# Power_Switching_Circuit_rev4.net
KiCad netlist of a schematic drawn in EAGLE
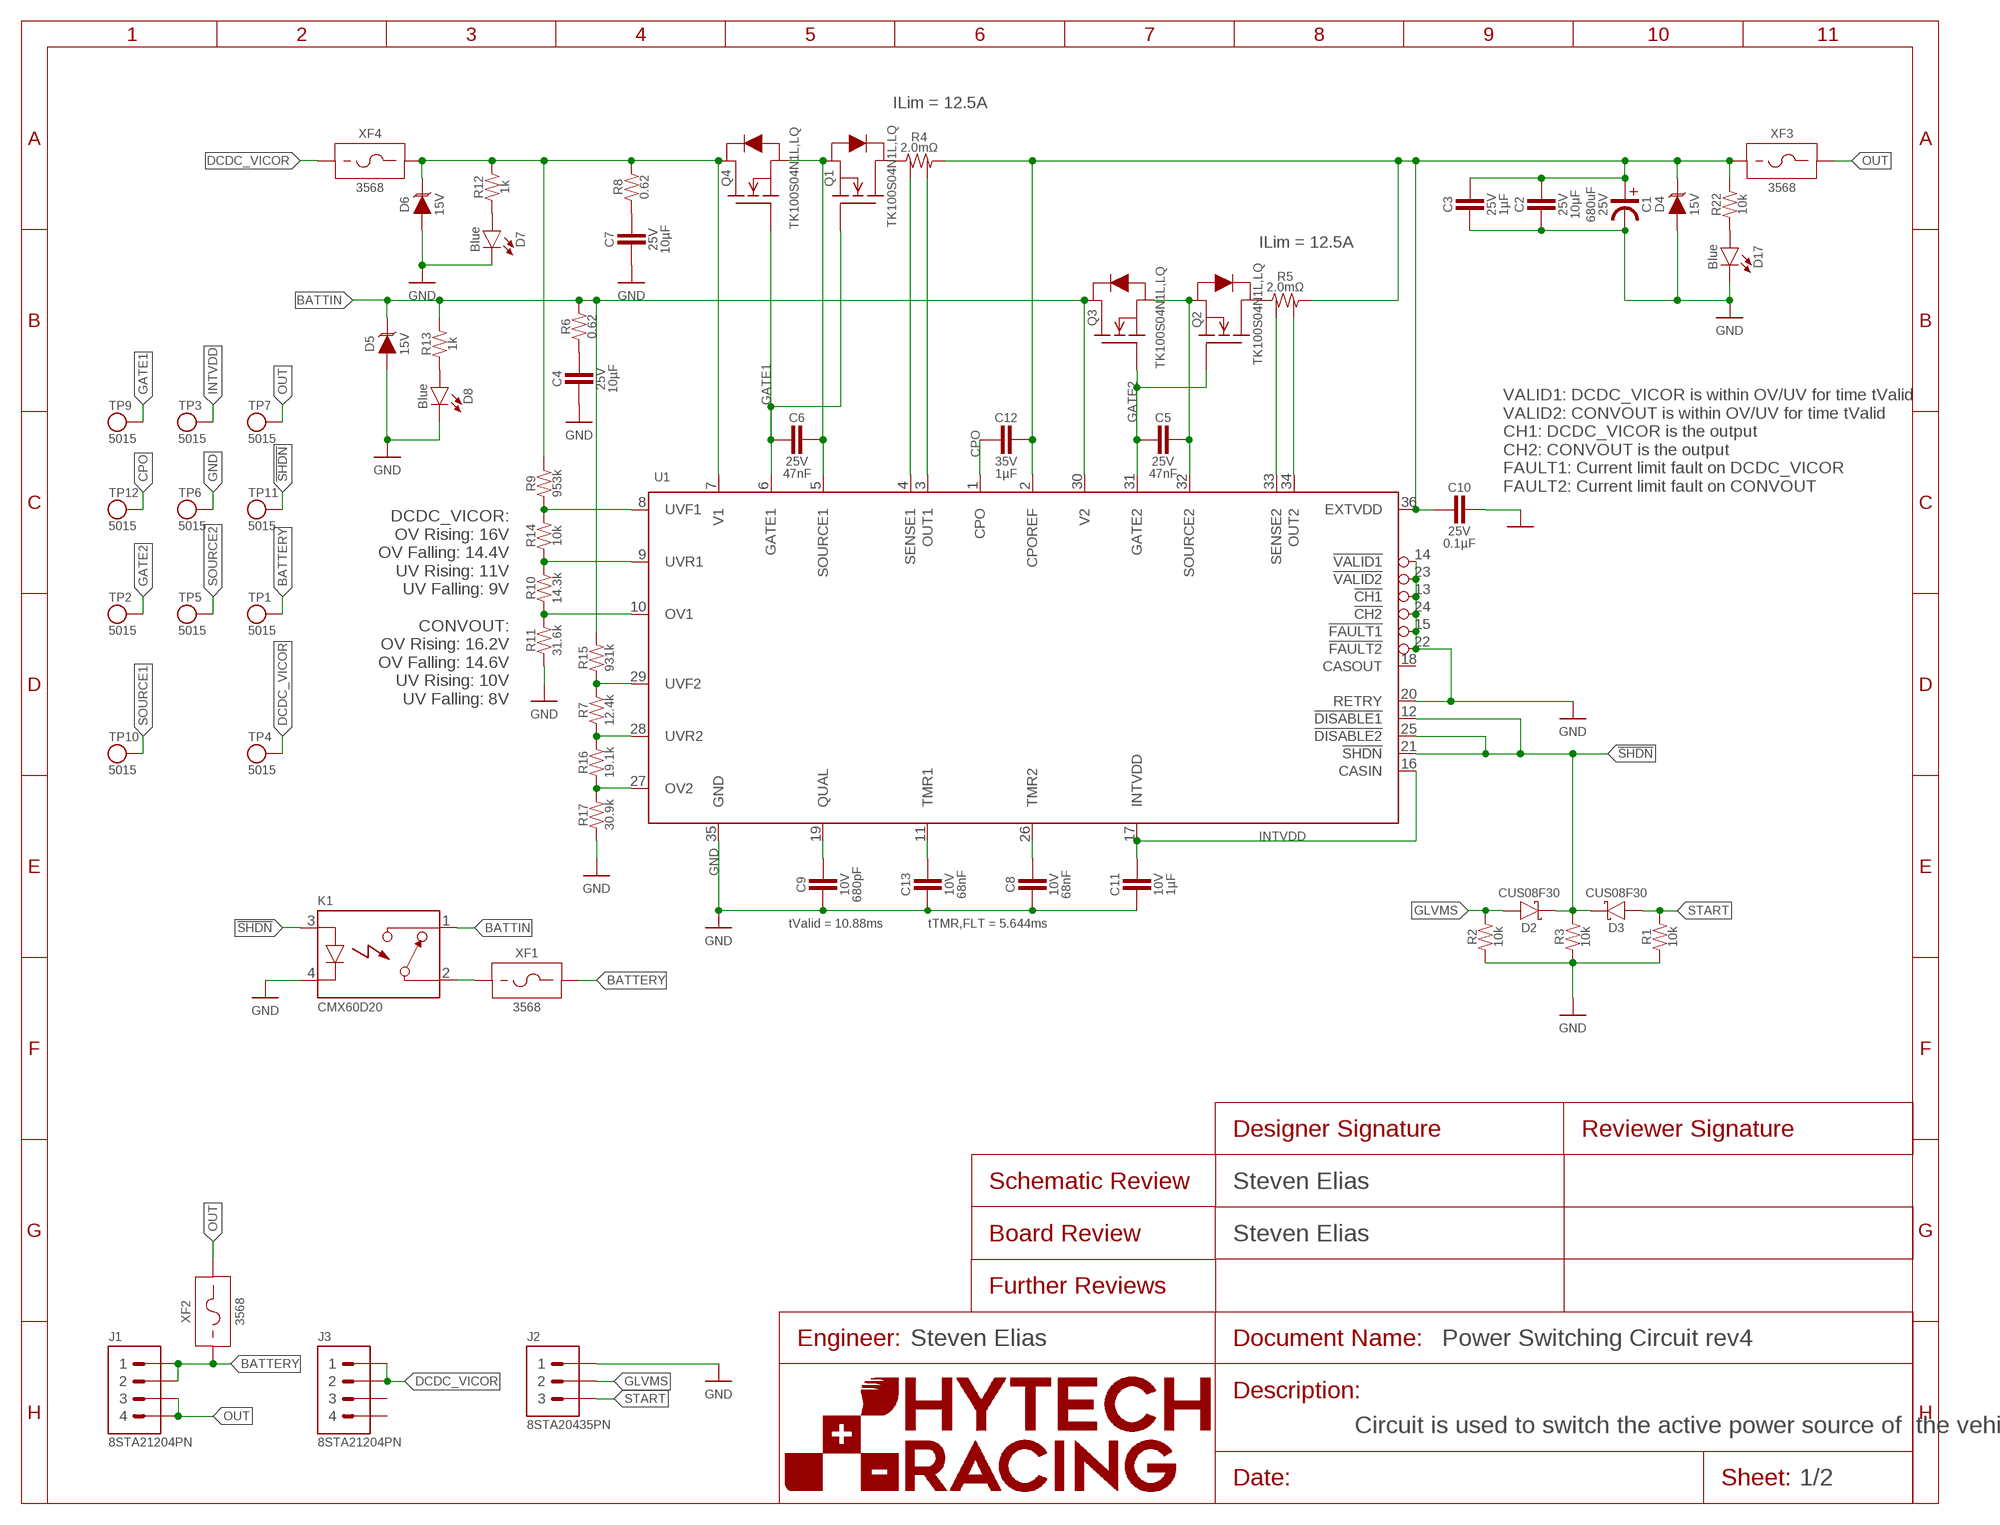
[diagram p0: schematic, sheet 1]
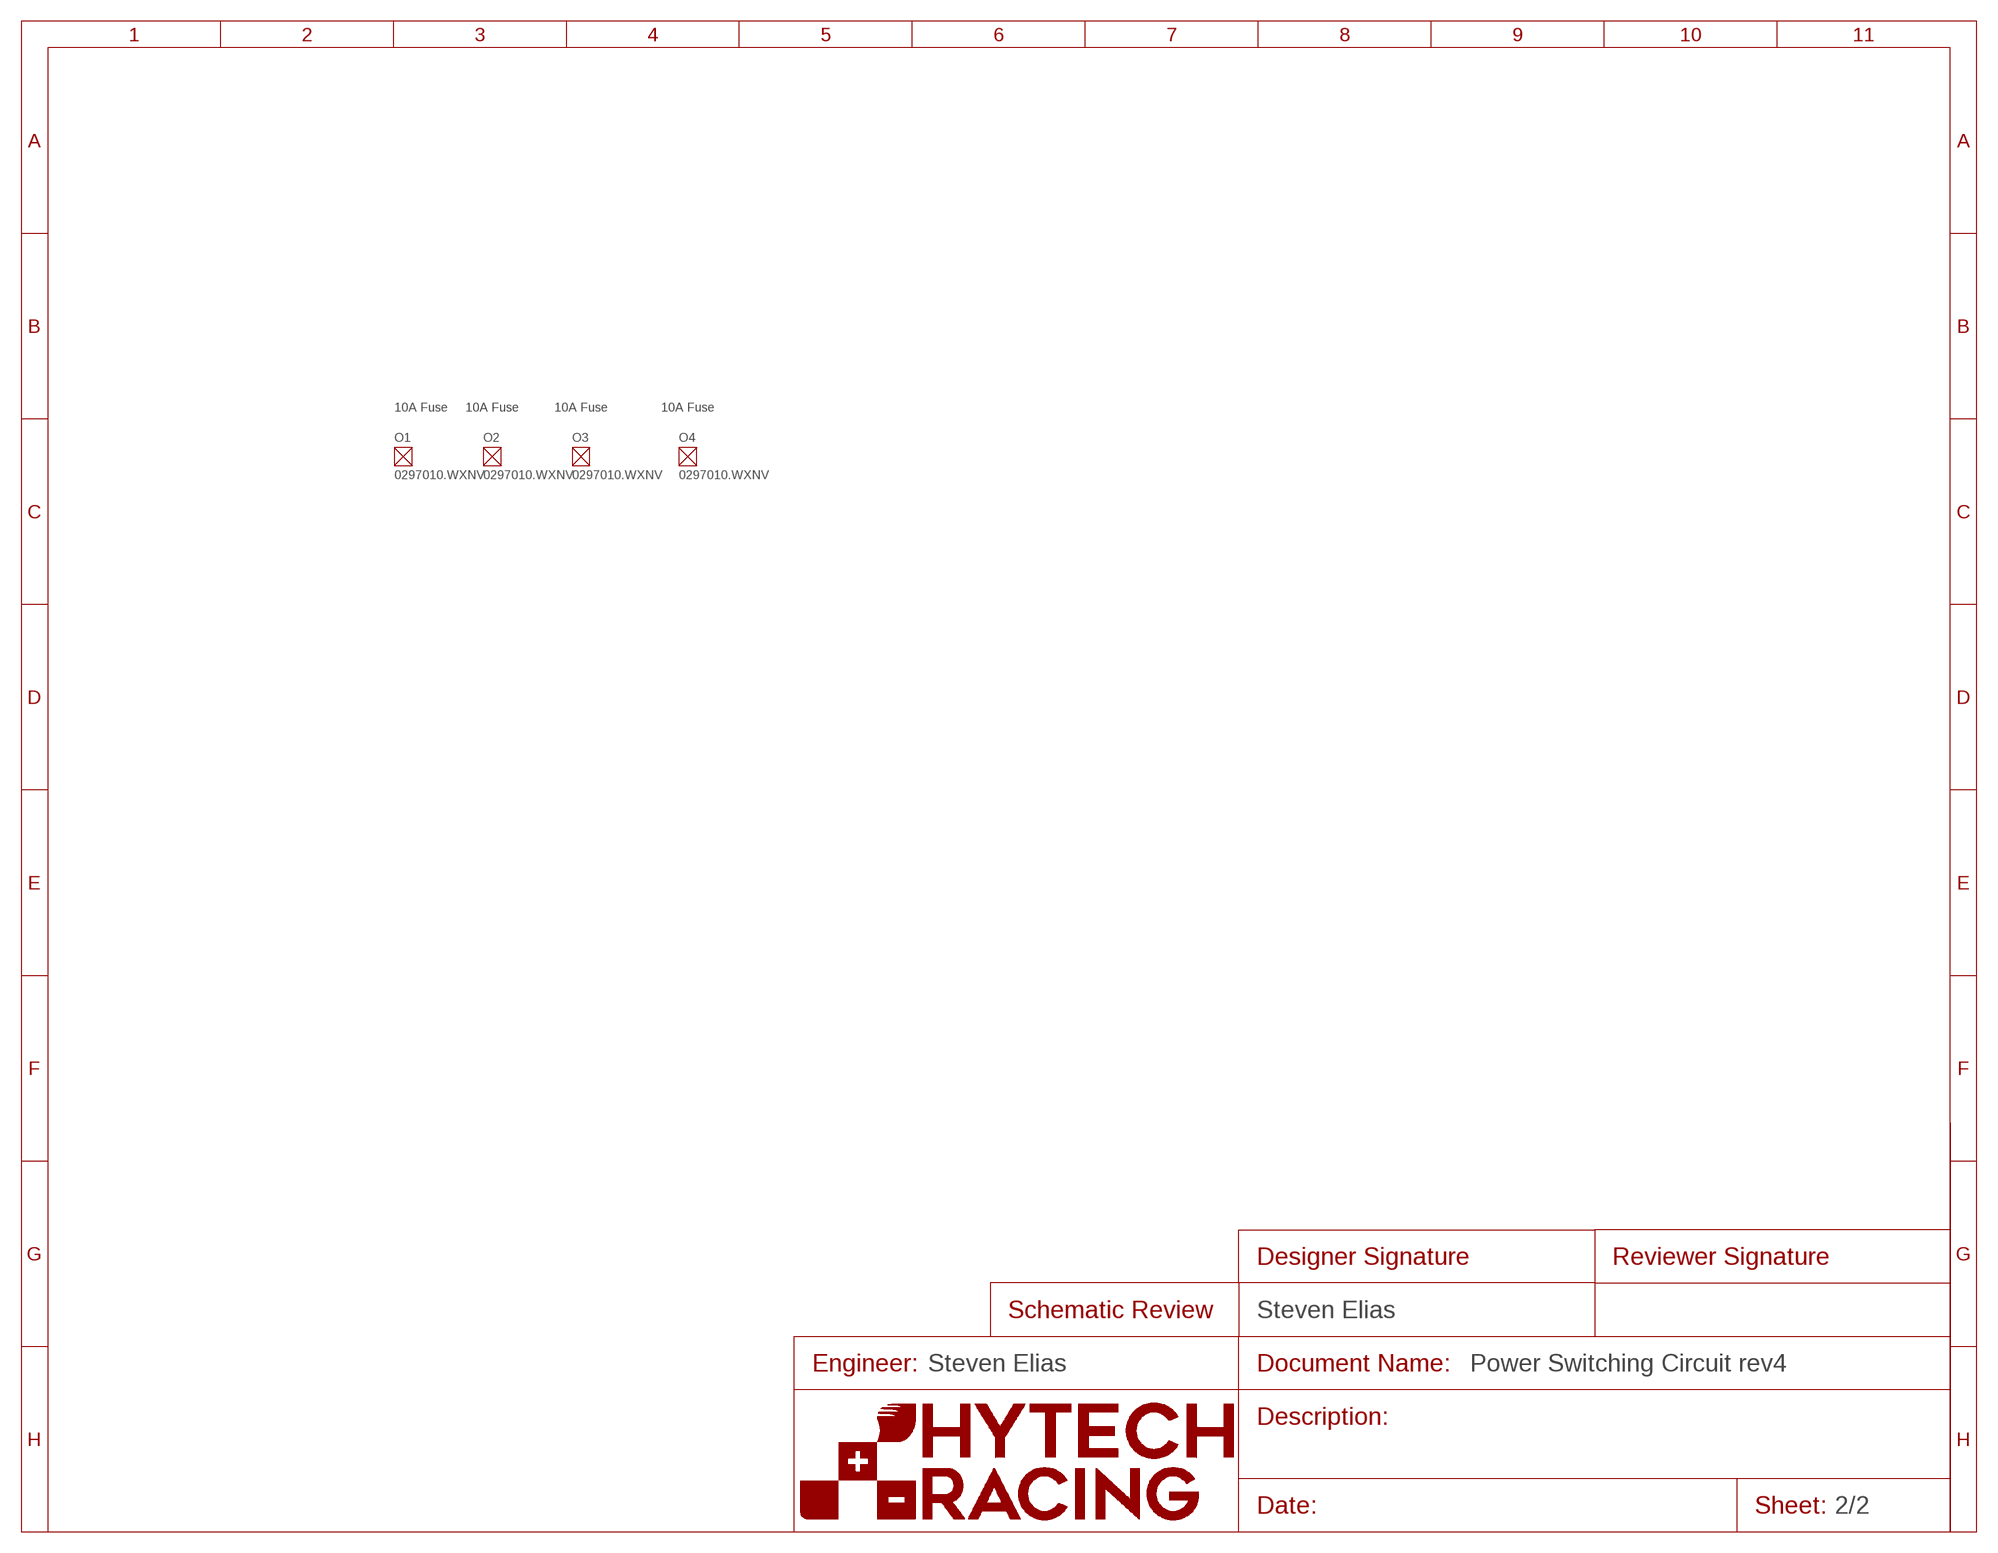
[diagram p1: schematic, sheet 2]

(export (version "E")
  (design (tool "Eeschema 10.0.6"))
  (components
    (comp (ref "C1")
      (value "EEUFP1E681")
      (footprint "eagle-import:EEUFP1E_")
      (fields
        (field (name "CAPACITANCE") "680uF")
        (field (name "MANUFACTURER") "Panasonic Electronic Components")
        (field (name "MPN") "EEU-FP1E681")
        (field (name "TOLERANCE") "20%")
        (field (name "VOLTAGE") "25V")
      )
      (libsource (lib "eagle-import") (part "EEUFP1E681"))
    )
    (comp (ref "C2")
      (value "CAPACITOR_0603_25V_10UF")
      (footprint "eagle-import:0603-CAP")
      (fields
        (field (name "CAPACITANCE") "10µF")
        (field (name "MANUFACTURER") "Murata Electronics")
        (field (name "MPN") "GRM188R61E106MA73D")
        (field (name "TOLERANCE") "20%")
        (field (name "VOLTAGE") "25V")
      )
      (libsource (lib "eagle-import") (part "CAPACITOR_?_060325V_10UF"))
    )
    (comp (ref "C3")
      (value "CAPACITOR_0603_25V_1UF")
      (footprint "eagle-import:0603-CAP")
      (fields
        (field (name "CAPACITANCE") "1µF")
        (field (name "MANUFACTURER") "Samsung Electro-Mechanics")
        (field (name "MPN") "CL10B105KA8NNNC")
        (field (name "TOLERANCE") "10%")
        (field (name "VOLTAGE") "25V")
      )
      (libsource (lib "eagle-import") (part "CAPACITOR_?_060325V_1UF"))
    )
    (comp (ref "C4")
      (value "CAPACITOR_0603_25V_10UF")
      (footprint "eagle-import:0603-CAP")
      (fields
        (field (name "CAPACITANCE") "10µF")
        (field (name "MANUFACTURER") "Murata Electronics")
        (field (name "MPN") "GRM188R61E106MA73D")
        (field (name "TOLERANCE") "20%")
        (field (name "VOLTAGE") "25V")
      )
      (libsource (lib "eagle-import") (part "CAPACITOR_?_060325V_10UF"))
    )
    (comp (ref "C5")
      (value "CAPACITOR_0603_25V_47NF")
      (footprint "eagle-import:0603-CAP")
      (fields
        (field (name "CAPACITANCE") "47nF")
        (field (name "MANUFACTURER") "Kyocera AVX")
        (field (name "MPN") "06033C473K4Z2A")
        (field (name "TOLERANCE") "10%")
        (field (name "VOLTAGE") "25V")
      )
      (libsource (lib "eagle-import") (part "CAPACITOR_?_060325V_47NF"))
    )
    (comp (ref "C6")
      (value "CAPACITOR_0603_25V_47NF")
      (footprint "eagle-import:0603-CAP")
      (fields
        (field (name "CAPACITANCE") "47nF")
        (field (name "MANUFACTURER") "Kyocera AVX")
        (field (name "MPN") "06033C473K4Z2A")
        (field (name "TOLERANCE") "10%")
        (field (name "VOLTAGE") "25V")
      )
      (libsource (lib "eagle-import") (part "CAPACITOR_?_060325V_47NF"))
    )
    (comp (ref "C7")
      (value "CAPACITOR_0603_25V_10UF")
      (footprint "eagle-import:0603-CAP")
      (fields
        (field (name "CAPACITANCE") "10µF")
        (field (name "MANUFACTURER") "Murata Electronics")
        (field (name "MPN") "GRM188R61E106MA73D")
        (field (name "TOLERANCE") "20%")
        (field (name "VOLTAGE") "25V")
      )
      (libsource (lib "eagle-import") (part "CAPACITOR_?_060325V_10UF"))
    )
    (comp (ref "C8")
      (value "CAPACITOR_0603_10V_68NF")
      (footprint "eagle-import:0603-CAP")
      (fields
        (field (name "CAPACITANCE") "68nF")
        (field (name "MANUFACTURER") "KEMET")
        (field (name "MPN") "C0603C683K8RACTU")
        (field (name "TOLERANCE") "10%")
        (field (name "VOLTAGE") "10V")
      )
      (libsource (lib "eagle-import") (part "CAPACITOR_?_060310V_68NF"))
    )
    (comp (ref "C9")
      (value "CAPACITOR_0603_10V_680PF")
      (footprint "eagle-import:0603-CAP")
      (fields
        (field (name "CAPACITANCE") "680pF")
        (field (name "MANUFACTURER") "Würth Elektronik")
        (field (name "MPN") "885012006013")
        (field (name "TOLERANCE") "5%")
        (field (name "VOLTAGE") "10V")
      )
      (libsource (lib "eagle-import") (part "CAPACITOR_?_060310V_680PF"))
    )
    (comp (ref "C10")
      (value "CAPACITOR_0603_25V_0.1UF")
      (footprint "eagle-import:0603-CAP")
      (fields
        (field (name "CAPACITANCE") "0.1µF")
        (field (name "MANUFACTURER") "Samsung Electro-Mechanics")
        (field (name "MPN") "CL10B104KA8NNNC")
        (field (name "TOLERANCE") "10%")
        (field (name "VOLTAGE") "25V")
      )
      (libsource (lib "eagle-import") (part "CAPACITOR_?_060325V_0.1UF"))
    )
    (comp (ref "C11")
      (value "CAPACITOR_0603_10V_1UF")
      (footprint "eagle-import:0603-CAP")
      (fields
        (field (name "CAPACITANCE") "1µF")
        (field (name "MANUFACTURER") "Yageo")
        (field (name "MPN") "CC0603KRX7R6BB105")
        (field (name "TOLERANCE") "10%")
        (field (name "VOLTAGE") "10V")
      )
      (libsource (lib "eagle-import") (part "CAPACITOR_?_060310V_1UF"))
    )
    (comp (ref "C12")
      (value "CAPACITOR_0603_35V_1UF")
      (footprint "eagle-import:0603-CAP")
      (fields
        (field (name "CAPACITANCE") "1µF")
        (field (name "MANUFACTURER") "TDK Corporation")
        (field (name "MPN") "C1608X7R1V105K080AE")
        (field (name "TOLERANCE") "10%")
        (field (name "VOLTAGE") "35V")
      )
      (libsource (lib "eagle-import") (part "CAPACITOR_?_060335V_1UF"))
    )
    (comp (ref "C13")
      (value "CAPACITOR_0603_10V_68NF")
      (footprint "eagle-import:0603-CAP")
      (fields
        (field (name "CAPACITANCE") "68nF")
        (field (name "MANUFACTURER") "KEMET")
        (field (name "MPN") "C0603C683K8RACTU")
        (field (name "TOLERANCE") "10%")
        (field (name "VOLTAGE") "10V")
      )
      (libsource (lib "eagle-import") (part "CAPACITOR_?_060310V_68NF"))
    )
    (comp (ref "D2")
      (value "SCHOTTKY_SOD323_30V")
      (footprint "eagle-import:SOD-323")
      (fields
        (field (name "MANUFACTURER") "Toshiba Semiconductor and Storage")
        (field (name "MPN") "CUS08F30")
        (field (name "VOLTAGE") "30V")
      )
      (libsource (lib "eagle-import") (part "SCHOTTKY_?_SOD32330V"))
    )
    (comp (ref "D3")
      (value "SCHOTTKY_SOD323_30V")
      (footprint "eagle-import:SOD-323")
      (fields
        (field (name "MANUFACTURER") "Toshiba Semiconductor and Storage")
        (field (name "MPN") "CUS08F30")
        (field (name "VOLTAGE") "30V")
      )
      (libsource (lib "eagle-import") (part "SCHOTTKY_?_SOD32330V"))
    )
    (comp (ref "D4")
      (value "TVS_15V")
      (footprint "eagle-import:SOT-23")
      (fields
        (field (name "MANUFACTURER") "Vishay General Semiconductor - Diodes Division")
        (field (name "MPN") "GSOT15-E3-08")
        (field (name "VOLTAGE") "15V")
      )
      (libsource (lib "eagle-import") (part "TVS_15V"))
    )
    (comp (ref "D5")
      (value "TVS_15V")
      (footprint "eagle-import:SOT-23")
      (fields
        (field (name "MANUFACTURER") "Vishay General Semiconductor - Diodes Division")
        (field (name "MPN") "GSOT15-E3-08")
        (field (name "VOLTAGE") "15V")
      )
      (libsource (lib "eagle-import") (part "TVS_15V"))
    )
    (comp (ref "D6")
      (value "TVS_15V")
      (footprint "eagle-import:SOT-23")
      (fields
        (field (name "MANUFACTURER") "Vishay General Semiconductor - Diodes Division")
        (field (name "MPN") "GSOT15-E3-08")
        (field (name "VOLTAGE") "15V")
      )
      (libsource (lib "eagle-import") (part "TVS_15V"))
    )
    (comp (ref "D7")
      (value "LED_0603_BLUE")
      (footprint "eagle-import:0603-LED")
      (fields
        (field (name "COLOR") "Blue")
        (field (name "MANUFACTURER") "Kingbright")
        (field (name "MPN") "APT1608VBC/D")
      )
      (libsource (lib "eagle-import") (part "LED_?_0603BLUE"))
    )
    (comp (ref "D8")
      (value "LED_0603_BLUE")
      (footprint "eagle-import:0603-LED")
      (fields
        (field (name "COLOR") "Blue")
        (field (name "MANUFACTURER") "Kingbright")
        (field (name "MPN") "APT1608VBC/D")
      )
      (libsource (lib "eagle-import") (part "LED_?_0603BLUE"))
    )
    (comp (ref "D17")
      (value "LED_0603_BLUE")
      (footprint "eagle-import:0603-LED")
      (fields
        (field (name "COLOR") "Blue")
        (field (name "MANUFACTURER") "Kingbright")
        (field (name "MPN") "APT1608VBC/D")
      )
      (libsource (lib "eagle-import") (part "LED_?_0603BLUE"))
    )
    (comp (ref "J1")
      (value "CONNECTOR-4_SOURIAU_")
      (footprint "eagle-import:SOURIAU_12-04")
      (fields (field (name "MPN") "8STA21204PN") (field (name "MANUFACTURER") "Souriau"))
      (libsource (lib "eagle-import") (part "CONNECTOR-4_?_SOURIAU"))
    )
    (comp (ref "J2")
      (value "CONNECTOR-3_8STA20435PN")
      (footprint "eagle-import:SOURIAU_04-35")
      (fields (field (name "MANUFACTURER") "Souriau") (field (name "MPN") "8STA20435PN"))
      (libsource (lib "eagle-import") (part "CONNECTOR-3_?8STA20435PN"))
    )
    (comp (ref "J3")
      (value "CONNECTOR-4_SOURIAU_")
      (footprint "eagle-import:SOURIAU_12-04")
      (fields (field (name "MPN") "8STA21204PN") (field (name "MANUFACTURER") "Souriau"))
      (libsource (lib "eagle-import") (part "CONNECTOR-4_?_SOURIAU"))
    )
    (comp (ref "K1")
      (value "RELAY_SOLIDSTATE_NO_CMX60D20")
      (footprint "eagle-import:CRYDOM_CMX")
      (fields (field (name "MANUFACTURER") "Crydom") (field (name "MPN") "CMX60D20"))
      (libsource (lib "eagle-import") (part "RELAY_SOLIDSTATE_NO_?CMX60D20"))
    )
    (comp (ref "Q1")
      (value "TRANSISTOR_N_MOS_2-7K1S_TK100S04N1LLQ")
      (footprint "eagle-import:DPAK(2-7K1S)")
      (fields
        (field (name "MANUFACTURER") "Toshiba Semiconductor and Storage")
        (field (name "MPN") "TK100S04N1L,LQ")
      )
      (libsource (lib "eagle-import") (part "TRANSISTOR_N_MOS_?_2-7K1STK100S04N1LLQ"))
    )
    (comp (ref "Q2")
      (value "TRANSISTOR_N_MOS_2-7K1S_TK100S04N1LLQ")
      (footprint "eagle-import:DPAK(2-7K1S)")
      (fields
        (field (name "MANUFACTURER") "Toshiba Semiconductor and Storage")
        (field (name "MPN") "TK100S04N1L,LQ")
      )
      (libsource (lib "eagle-import") (part "TRANSISTOR_N_MOS_?_2-7K1STK100S04N1LLQ"))
    )
    (comp (ref "Q3")
      (value "TRANSISTOR_N_MOS_2-7K1S_TK100S04N1LLQ")
      (footprint "eagle-import:DPAK(2-7K1S)")
      (fields
        (field (name "MANUFACTURER") "Toshiba Semiconductor and Storage")
        (field (name "MPN") "TK100S04N1L,LQ")
      )
      (libsource (lib "eagle-import") (part "TRANSISTOR_N_MOS_?_2-7K1STK100S04N1LLQ"))
    )
    (comp (ref "Q4")
      (value "TRANSISTOR_N_MOS_2-7K1S_TK100S04N1LLQ")
      (footprint "eagle-import:DPAK(2-7K1S)")
      (fields
        (field (name "MANUFACTURER") "Toshiba Semiconductor and Storage")
        (field (name "MPN") "TK100S04N1L,LQ")
      )
      (libsource (lib "eagle-import") (part "TRANSISTOR_N_MOS_?_2-7K1STK100S04N1LLQ"))
    )
    (comp (ref "R1")
      (value "RESISTOR_0603_10K")
      (footprint "eagle-import:0603-RES")
      (fields
        (field (name "MANUFACTURER") "Yageo")
        (field (name "MPN") "RC0603FR-0710KL")
        (field (name "POWER") "0.1W")
        (field (name "RESISTANCE") "10k")
      )
      (libsource (lib "eagle-import") (part "RESISTOR_?_060310K"))
    )
    (comp (ref "R2")
      (value "RESISTOR_0603_10K")
      (footprint "eagle-import:0603-RES")
      (fields
        (field (name "MANUFACTURER") "Yageo")
        (field (name "MPN") "RC0603FR-0710KL")
        (field (name "POWER") "0.1W")
        (field (name "RESISTANCE") "10k")
      )
      (libsource (lib "eagle-import") (part "RESISTOR_?_060310K"))
    )
    (comp (ref "R3")
      (value "RESISTOR_0603_10K")
      (footprint "eagle-import:0603-RES")
      (fields
        (field (name "MANUFACTURER") "Yageo")
        (field (name "MPN") "RC0603FR-0710KL")
        (field (name "POWER") "0.1W")
        (field (name "RESISTANCE") "10k")
      )
      (libsource (lib "eagle-import") (part "RESISTOR_?_060310K"))
    )
    (comp (ref "R4")
      (value "RESISTOR_SENSE__WSL40262L000FEB")
      (footprint "eagle-import:4026")
      (fields
        (field (name "MANUFACTURER") "Vishay Dale")
        (field (name "MPN") "WSL40262L000FEB")
        (field (name "POWER") "3W")
        (field (name "RESISTANCE") "2.0mΩ")
      )
      (libsource (lib "eagle-import") (part "RESISTOR_SENSE_?_WSL40262L000FEB"))
    )
    (comp (ref "R5")
      (value "RESISTOR_SENSE__WSL40262L000FEB")
      (footprint "eagle-import:4026")
      (fields
        (field (name "MANUFACTURER") "Vishay Dale")
        (field (name "MPN") "WSL40262L000FEB")
        (field (name "POWER") "3W")
        (field (name "RESISTANCE") "2.0mΩ")
      )
      (libsource (lib "eagle-import") (part "RESISTOR_SENSE_?_WSL40262L000FEB"))
    )
    (comp (ref "R6")
      (value "RESISTOR_0805_0.62")
      (footprint "eagle-import:0805-RES")
      (fields
        (field (name "MANUFACTURER") "Yageo")
        (field (name "MPN") "RL0805FR-070R62L")
        (field (name "POWER") "0.125W")
        (field (name "RESISTANCE") "0.62")
      )
      (libsource (lib "eagle-import") (part "RESISTOR_?_08050.62"))
    )
    (comp (ref "R7")
      (value "RESISTOR_0603_12.4K")
      (footprint "eagle-import:0603-RES")
      (fields
        (field (name "MANUFACTURER") "Panasonic Electronic Components")
        (field (name "MPN") "ERJ-PB3B1242V")
        (field (name "POWER") "0.2W")
        (field (name "RESISTANCE") "12.4k")
      )
      (libsource (lib "eagle-import") (part "RESISTOR_?_060312.4K"))
    )
    (comp (ref "R8")
      (value "RESISTOR_0805_0.62")
      (footprint "eagle-import:0805-RES")
      (fields
        (field (name "MANUFACTURER") "Yageo")
        (field (name "MPN") "RL0805FR-070R62L")
        (field (name "POWER") "0.125W")
        (field (name "RESISTANCE") "0.62")
      )
      (libsource (lib "eagle-import") (part "RESISTOR_?_08050.62"))
    )
    (comp (ref "R9")
      (value "RESISTOR_0805_953K")
      (footprint "eagle-import:0805-RES")
      (fields
        (field (name "MANUFACTURER") "Panasonic Electronic Components")
        (field (name "MPN") "ERJ-6ENF9533V")
        (field (name "POWER") "0.125W")
        (field (name "RESISTANCE") "953k")
      )
      (libsource (lib "eagle-import") (part "RESISTOR_?_0805953K"))
    )
    (comp (ref "R10")
      (value "RESISTOR_0805_14.3K")
      (footprint "eagle-import:0805-RES")
      (fields
        (field (name "MANUFACTURER") "Panasonic Electronic Components")
        (field (name "MPN") "ERJ-6ENF1432V")
        (field (name "POWER") "0.125W")
        (field (name "RESISTANCE") "14.3k")
      )
      (libsource (lib "eagle-import") (part "RESISTOR_?_080514.3K"))
    )
    (comp (ref "R11")
      (value "RESISTOR_0805_31.6K")
      (footprint "eagle-import:0805-RES")
      (fields
        (field (name "MANUFACTURER") "Vishay Dale")
        (field (name "MPN") "CRCW060331K6FKEAHP")
        (field (name "POWER") "0.33W")
        (field (name "RESISTANCE") "31.6k")
      )
      (libsource (lib "eagle-import") (part "RESISTOR_?_080531.6K"))
    )
    (comp (ref "R12")
      (value "RESISTOR_0603_1K")
      (footprint "eagle-import:0603-RES")
      (fields
        (field (name "MANUFACTURER") "Yageo")
        (field (name "MPN") "RC0603FR-071KL")
        (field (name "POWER") "0.1W")
        (field (name "RESISTANCE") "1k")
      )
      (libsource (lib "eagle-import") (part "RESISTOR_?_06031K"))
    )
    (comp (ref "R13")
      (value "RESISTOR_0603_1K")
      (footprint "eagle-import:0603-RES")
      (fields
        (field (name "MANUFACTURER") "Yageo")
        (field (name "MPN") "RC0603FR-071KL")
        (field (name "POWER") "0.1W")
        (field (name "RESISTANCE") "1k")
      )
      (libsource (lib "eagle-import") (part "RESISTOR_?_06031K"))
    )
    (comp (ref "R14")
      (value "RESISTOR_0603_10K")
      (footprint "eagle-import:0603-RES")
      (fields
        (field (name "MANUFACTURER") "Yageo")
        (field (name "MPN") "RC0603FR-0710KL")
        (field (name "POWER") "0.1W")
        (field (name "RESISTANCE") "10k")
      )
      (libsource (lib "eagle-import") (part "RESISTOR_?_060310K"))
    )
    (comp (ref "R15")
      (value "RESISTOR_0805_931K")
      (footprint "eagle-import:0805-RES")
      (fields
        (field (name "MANUFACTURER") "Panasonic Electronic Components")
        (field (name "MPN") "ERJ-PB6B9313V")
        (field (name "POWER") "0.25W")
        (field (name "RESISTANCE") "931k")
      )
      (libsource (lib "eagle-import") (part "RESISTOR_?_0805931K"))
    )
    (comp (ref "R16")
      (value "RESISTOR_0805_19.1K")
      (footprint "eagle-import:0805-RES")
      (fields
        (field (name "MANUFACTURER") "Panasonic Electronic Components")
        (field (name "MPN") "ERJ-6ENF1912V")
        (field (name "POWER") "0.125W")
        (field (name "RESISTANCE") "19.1k")
      )
      (libsource (lib "eagle-import") (part "RESISTOR_?_080519.1K"))
    )
    (comp (ref "R17")
      (value "RESISTOR_0603_30.9K")
      (footprint "eagle-import:0603-RES")
      (fields
        (field (name "MANUFACTURER") "Panasonic Electronic Components")
        (field (name "MPN") "ERJ-PB3B3092V")
        (field (name "POWER") "0.25W")
        (field (name "RESISTANCE") "30.9k")
      )
      (libsource (lib "eagle-import") (part "RESISTOR_?_060330.9K"))
    )
    (comp (ref "R22")
      (value "RESISTOR_0603_10K")
      (footprint "eagle-import:0603-RES")
      (fields
        (field (name "MANUFACTURER") "Yageo")
        (field (name "MPN") "RC0603FR-0710KL")
        (field (name "POWER") "0.1W")
        (field (name "RESISTANCE") "10k")
      )
      (libsource (lib "eagle-import") (part "RESISTOR_?_060310K"))
    )
    (comp (ref "TP1")
      (value "TEST_POINT")
      (footprint "eagle-import:5015")
      (fields (field (name "MPN") "5015") (field (name "MANUFACTURER") "Keystone Electronics"))
      (libsource (lib "eagle-import") (part "TEST_POINT"))
    )
    (comp (ref "TP2")
      (value "TEST_POINT")
      (footprint "eagle-import:5015")
      (fields (field (name "MPN") "5015") (field (name "MANUFACTURER") "Keystone Electronics"))
      (libsource (lib "eagle-import") (part "TEST_POINT"))
    )
    (comp (ref "TP3")
      (value "INTVDD")
      (footprint "eagle-import:5015")
      (fields (field (name "MPN") "5015") (field (name "MANUFACTURER") "Keystone Electronics"))
      (libsource (lib "eagle-import") (part "TEST_POINT"))
    )
    (comp (ref "TP4")
      (value "TEST_POINT")
      (footprint "eagle-import:5015")
      (fields (field (name "MPN") "5015") (field (name "MANUFACTURER") "Keystone Electronics"))
      (libsource (lib "eagle-import") (part "TEST_POINT"))
    )
    (comp (ref "TP5")
      (value "TEST_POINT")
      (footprint "eagle-import:5015")
      (fields (field (name "MPN") "5015") (field (name "MANUFACTURER") "Keystone Electronics"))
      (libsource (lib "eagle-import") (part "TEST_POINT"))
    )
    (comp (ref "TP6")
      (value "TEST_POINT")
      (footprint "eagle-import:5015")
      (fields (field (name "MPN") "5015") (field (name "MANUFACTURER") "Keystone Electronics"))
      (libsource (lib "eagle-import") (part "TEST_POINT"))
    )
    (comp (ref "TP7")
      (value "TEST_POINT")
      (footprint "eagle-import:5015")
      (fields (field (name "MPN") "5015") (field (name "MANUFACTURER") "Keystone Electronics"))
      (libsource (lib "eagle-import") (part "TEST_POINT"))
    )
    (comp (ref "TP9")
      (value "TEST_POINT")
      (footprint "eagle-import:5015")
      (fields (field (name "MPN") "5015") (field (name "MANUFACTURER") "Keystone Electronics"))
      (libsource (lib "eagle-import") (part "TEST_POINT"))
    )
    (comp (ref "TP10")
      (value "TEST_POINT")
      (footprint "eagle-import:5015")
      (fields (field (name "MPN") "5015") (field (name "MANUFACTURER") "Keystone Electronics"))
      (libsource (lib "eagle-import") (part "TEST_POINT"))
    )
    (comp (ref "TP11")
      (value "TEST_POINT")
      (footprint "eagle-import:5015")
      (fields (field (name "MPN") "5015") (field (name "MANUFACTURER") "Keystone Electronics"))
      (libsource (lib "eagle-import") (part "TEST_POINT"))
    )
    (comp (ref "TP12")
      (value "TEST_POINT")
      (footprint "eagle-import:5015")
      (fields (field (name "MPN") "5015") (field (name "MANUFACTURER") "Keystone Electronics"))
      (libsource (lib "eagle-import") (part "TEST_POINT"))
    )
    (comp (ref "U1")
      (value "LTC4421")
      (footprint "eagle-import:SSOP-36")
      (fields (field (name "MPN") "LTC4421CG#PBF") (field (name "MANUFACTURER") "Analog Devices Inc."))
      (libsource (lib "eagle-import") (part "LTC4421"))
    )
    (comp (ref "XF1")
      (value "FUSE_HOLDER_MINIBLADEPTH")
      (footprint "eagle-import:3568")
      (fields (field (name "MANUFACTURER") "Keystone") (field (name "MPN") "3568"))
      (libsource (lib "eagle-import") (part "FUSE_HOLDER_PTHMINIBLADE"))
    )
    (comp (ref "XF2")
      (value "FUSE_HOLDER_MINIBLADEPTH")
      (footprint "eagle-import:3568")
      (fields (field (name "MANUFACTURER") "Keystone") (field (name "MPN") "3568"))
      (libsource (lib "eagle-import") (part "FUSE_HOLDER_PTHMINIBLADE"))
    )
    (comp (ref "XF3")
      (value "FUSE_HOLDER_MINIBLADEPTH")
      (footprint "eagle-import:3568")
      (fields (field (name "MANUFACTURER") "Keystone") (field (name "MPN") "3568"))
      (libsource (lib "eagle-import") (part "FUSE_HOLDER_PTHMINIBLADE"))
    )
    (comp (ref "XF4")
      (value "FUSE_HOLDER_MINIBLADEPTH")
      (footprint "eagle-import:3568")
      (fields (field (name "MANUFACTURER") "Keystone") (field (name "MPN") "3568"))
      (libsource (lib "eagle-import") (part "FUSE_HOLDER_PTHMINIBLADE"))
    )
  )
  (nets
    (net (code "1") (name "BATTERY") (class "Default")
      (node (ref "J1") (pin "1") (pinfunction "1_1") (pintype "passive"))
      (node (ref "J1") (pin "2") (pinfunction "2_2") (pintype "passive"))
      (node (ref "TP1") (pin "1") (pinfunction "1_1") (pintype "passive"))
      (node (ref "XF1") (pin "3") (pinfunction "2_3") (pintype "passive"))
      (node (ref "XF1") (pin "4") (pinfunction "2_4") (pintype "passive"))
      (node (ref "XF2") (pin "1") (pinfunction "1_1") (pintype "passive"))
      (node (ref "XF2") (pin "2") (pinfunction "1_2") (pintype "passive"))
    )
    (net (code "2") (name "BATTIN") (class "Default")
      (node (ref "D5") (pin "3") (pinfunction "C_3") (pintype "passive"))
      (node (ref "K1") (pin "1") (pinfunction "CONTACT2_1") (pintype "bidirectional"))
      (node (ref "Q3") (pin "2") (pinfunction "D_2") (pintype "passive"))
      (node (ref "R13") (pin "2") (pinfunction "2_2") (pintype "passive"))
      (node (ref "R15") (pin "2") (pinfunction "2_2") (pintype "passive"))
      (node (ref "R6") (pin "2") (pinfunction "2_2") (pintype "passive"))
      (node (ref "U1") (pin "30") (pinfunction "V2_30") (pintype "input"))
    )
    (net (code "3") (name "CPO") (class "Default")
      (node (ref "C12") (pin "2") (pinfunction "2_2") (pintype "passive"))
      (node (ref "TP12") (pin "1") (pinfunction "1_1") (pintype "passive"))
      (node (ref "U1") (pin "1") (pinfunction "CPO_1") (pintype "input"))
    )
    (net (code "4") (name "DCDC_VICOR") (class "Default")
      (node (ref "J3") (pin "1") (pinfunction "1_1") (pintype "passive"))
      (node (ref "J3") (pin "2") (pinfunction "2_2") (pintype "passive"))
      (node (ref "TP4") (pin "1") (pinfunction "1_1") (pintype "passive"))
      (node (ref "XF4") (pin "1") (pinfunction "1_1") (pintype "passive"))
      (node (ref "XF4") (pin "2") (pinfunction "1_2") (pintype "passive"))
    )
    (net (code "5") (name "GATE1") (class "Default")
      (node (ref "C6") (pin "2") (pinfunction "2_2") (pintype "passive"))
      (node (ref "Q1") (pin "1") (pinfunction "G_1") (pintype "passive"))
      (node (ref "Q4") (pin "1") (pinfunction "G_1") (pintype "passive"))
      (node (ref "TP9") (pin "1") (pinfunction "1_1") (pintype "passive"))
      (node (ref "U1") (pin "6") (pinfunction "GATE1_6") (pintype "input"))
    )
    (net (code "6") (name "GATE2") (class "Default")
      (node (ref "C5") (pin "2") (pinfunction "2_2") (pintype "passive"))
      (node (ref "Q2") (pin "1") (pinfunction "G_1") (pintype "passive"))
      (node (ref "Q3") (pin "1") (pinfunction "G_1") (pintype "passive"))
      (node (ref "TP2") (pin "1") (pinfunction "1_1") (pintype "passive"))
      (node (ref "U1") (pin "31") (pinfunction "GATE2_31") (pintype "input"))
    )
    (net (code "7") (name "GLVMS") (class "Default")
      (node (ref "D2") (pin "A") (pinfunction "A_A") (pintype "passive"))
      (node (ref "J2") (pin "B") (pinfunction "2_B") (pintype "passive"))
      (node (ref "R2") (pin "2") (pinfunction "2_2") (pintype "passive"))
    )
    (net (code "8") (name "GND") (class "Default")
      (node (ref "C1") (pin "P$2") (pinfunction "MINUS_P$2") (pintype "passive"))
      (node (ref "C10") (pin "1") (pinfunction "1_1") (pintype "passive"))
      (node (ref "C11") (pin "2") (pinfunction "2_2") (pintype "passive"))
      (node (ref "C13") (pin "2") (pinfunction "2_2") (pintype "passive"))
      (node (ref "C2") (pin "2") (pinfunction "2_2") (pintype "passive"))
      (node (ref "C3") (pin "2") (pinfunction "2_2") (pintype "passive"))
      (node (ref "C4") (pin "2") (pinfunction "2_2") (pintype "passive"))
      (node (ref "C7") (pin "2") (pinfunction "2_2") (pintype "passive"))
      (node (ref "C8") (pin "2") (pinfunction "2_2") (pintype "passive"))
      (node (ref "C9") (pin "2") (pinfunction "2_2") (pintype "passive"))
      (node (ref "D17") (pin "1") (pinfunction "C_1") (pintype "passive"))
      (node (ref "D4") (pin "1") (pinfunction "A_1") (pintype "passive"))
      (node (ref "D5") (pin "1") (pinfunction "A_1") (pintype "passive"))
      (node (ref "D6") (pin "1") (pinfunction "A_1") (pintype "passive"))
      (node (ref "D7") (pin "1") (pinfunction "C_1") (pintype "passive"))
      (node (ref "D8") (pin "1") (pinfunction "C_1") (pintype "passive"))
      (node (ref "J2") (pin "A") (pinfunction "1_A") (pintype "passive"))
      (node (ref "K1") (pin "4") (pinfunction "CONTROL-_4") (pintype "passive"))
      (node (ref "R1") (pin "1") (pinfunction "1_1") (pintype "passive"))
      (node (ref "R11") (pin "1") (pinfunction "1_1") (pintype "passive"))
      (node (ref "R17") (pin "1") (pinfunction "1_1") (pintype "passive"))
      (node (ref "R2") (pin "1") (pinfunction "1_1") (pintype "passive"))
      (node (ref "R3") (pin "1") (pinfunction "1_1") (pintype "passive"))
      (node (ref "TP6") (pin "1") (pinfunction "1_1") (pintype "passive"))
      (node (ref "U1") (pin "13") (pinfunction "~{CH1}_13") (pintype "open_collector"))
      (node (ref "U1") (pin "14") (pinfunction "~{VALID1}_14") (pintype "open_collector"))
      (node (ref "U1") (pin "15") (pinfunction "~{FAULT1}_15") (pintype "open_collector"))
      (node (ref "U1") (pin "20") (pinfunction "RETRY_20") (pintype "input"))
      (node (ref "U1") (pin "22") (pinfunction "~{FAULT2}_22") (pintype "open_collector"))
      (node (ref "U1") (pin "23") (pinfunction "~{VALID2}_23") (pintype "open_collector"))
      (node (ref "U1") (pin "24") (pinfunction "~{CH2}_24") (pintype "open_collector"))
      (node (ref "U1") (pin "35") (pinfunction "GND_35") (pintype "power_in"))
    )
    (net (code "9") (name "INTVDD") (class "Default")
      (node (ref "C11") (pin "1") (pinfunction "1_1") (pintype "passive"))
      (node (ref "TP3") (pin "1") (pinfunction "1_1") (pintype "passive"))
      (node (ref "U1") (pin "16") (pinfunction "CASIN_16") (pintype "input"))
      (node (ref "U1") (pin "17") (pinfunction "INTVDD_17") (pintype "power_in"))
    )
    (net (code "10") (name "Net-(C1-PLUS)") (class "Default")
      (node (ref "C1") (pin "P$1") (pinfunction "PLUS_P$1") (pintype "passive"))
      (node (ref "C10") (pin "2") (pinfunction "2_2") (pintype "passive"))
      (node (ref "C12") (pin "1") (pinfunction "1_1") (pintype "passive"))
      (node (ref "C2") (pin "1") (pinfunction "1_1") (pintype "passive"))
      (node (ref "C3") (pin "1") (pinfunction "1_1") (pintype "passive"))
      (node (ref "D4") (pin "3") (pinfunction "C_3") (pintype "passive"))
      (node (ref "R22") (pin "2") (pinfunction "2_2") (pintype "passive"))
      (node (ref "R4") (pin "2") (pinfunction "2_2") (pintype "passive"))
      (node (ref "R5") (pin "2") (pinfunction "2_2") (pintype "passive"))
      (node (ref "U1") (pin "2") (pinfunction "CPOREF_2") (pintype "input"))
      (node (ref "U1") (pin "36") (pinfunction "EXTVDD_36") (pintype "power_in"))
      (node (ref "XF3") (pin "1") (pinfunction "1_1") (pintype "passive"))
      (node (ref "XF3") (pin "2") (pinfunction "1_2") (pintype "passive"))
    )
    (net (code "11") (name "Net-(C4-Pad1)") (class "Default")
      (node (ref "C4") (pin "1") (pinfunction "1_1") (pintype "passive"))
      (node (ref "R6") (pin "1") (pinfunction "1_1") (pintype "passive"))
    )
    (net (code "12") (name "Net-(C7-Pad1)") (class "Default")
      (node (ref "C7") (pin "1") (pinfunction "1_1") (pintype "passive"))
      (node (ref "R8") (pin "1") (pinfunction "1_1") (pintype "passive"))
    )
    (net (code "13") (name "Net-(D6-C)") (class "Default")
      (node (ref "D6") (pin "3") (pinfunction "C_3") (pintype "passive"))
      (node (ref "Q4") (pin "2") (pinfunction "D_2") (pintype "passive"))
      (node (ref "R12") (pin "2") (pinfunction "2_2") (pintype "passive"))
      (node (ref "R8") (pin "2") (pinfunction "2_2") (pintype "passive"))
      (node (ref "R9") (pin "2") (pinfunction "2_2") (pintype "passive"))
      (node (ref "U1") (pin "7") (pinfunction "V1_7") (pintype "input"))
      (node (ref "XF4") (pin "3") (pinfunction "2_3") (pintype "passive"))
      (node (ref "XF4") (pin "4") (pinfunction "2_4") (pintype "passive"))
    )
    (net (code "14") (name "Net-(D7-A)") (class "Default")
      (node (ref "D7") (pin "2") (pinfunction "A_2") (pintype "passive"))
      (node (ref "R12") (pin "1") (pinfunction "1_1") (pintype "passive"))
    )
    (net (code "15") (name "Net-(D8-A)") (class "Default")
      (node (ref "D8") (pin "2") (pinfunction "A_2") (pintype "passive"))
      (node (ref "R13") (pin "1") (pinfunction "1_1") (pintype "passive"))
    )
    (net (code "16") (name "Net-(D17-A)") (class "Default")
      (node (ref "D17") (pin "2") (pinfunction "A_2") (pintype "passive"))
      (node (ref "R22") (pin "1") (pinfunction "1_1") (pintype "passive"))
    )
    (net (code "17") (name "Net-(K1-CONTACT1)") (class "Default")
      (node (ref "K1") (pin "2") (pinfunction "CONTACT1_2") (pintype "bidirectional"))
      (node (ref "XF1") (pin "1") (pinfunction "1_1") (pintype "passive"))
      (node (ref "XF1") (pin "2") (pinfunction "1_2") (pintype "passive"))
    )
    (net (code "18") (name "Net-(Q1-D)") (class "Default")
      (node (ref "Q1") (pin "2") (pinfunction "D_2") (pintype "passive"))
      (node (ref "R4") (pin "1") (pinfunction "1_1") (pintype "passive"))
    )
    (net (code "19") (name "Net-(Q2-D)") (class "Default")
      (node (ref "Q2") (pin "2") (pinfunction "D_2") (pintype "passive"))
      (node (ref "R5") (pin "1") (pinfunction "1_1") (pintype "passive"))
    )
    (net (code "20") (name "Net-(U1-OUT1)") (class "Default")
      (node (ref "R4") (pin "4") (pinfunction "4_4") (pintype "passive"))
      (node (ref "U1") (pin "3") (pinfunction "OUT1_3") (pintype "input"))
    )
    (net (code "21") (name "Net-(U1-OUT2)") (class "Default")
      (node (ref "R5") (pin "4") (pinfunction "4_4") (pintype "passive"))
      (node (ref "U1") (pin "34") (pinfunction "OUT2_34") (pintype "input"))
    )
    (net (code "22") (name "Net-(U1-OV1)") (class "Default")
      (node (ref "R10") (pin "1") (pinfunction "1_1") (pintype "passive"))
      (node (ref "R11") (pin "2") (pinfunction "2_2") (pintype "passive"))
      (node (ref "U1") (pin "10") (pinfunction "OV1_10") (pintype "input"))
    )
    (net (code "23") (name "Net-(U1-OV2)") (class "Default")
      (node (ref "R16") (pin "1") (pinfunction "1_1") (pintype "passive"))
      (node (ref "R17") (pin "2") (pinfunction "2_2") (pintype "passive"))
      (node (ref "U1") (pin "27") (pinfunction "OV2_27") (pintype "input"))
    )
    (net (code "24") (name "Net-(U1-QUAL)") (class "Default")
      (node (ref "C9") (pin "1") (pinfunction "1_1") (pintype "passive"))
      (node (ref "U1") (pin "19") (pinfunction "QUAL_19") (pintype "bidirectional"))
    )
    (net (code "25") (name "Net-(U1-SENSE1)") (class "Default")
      (node (ref "R4") (pin "3") (pinfunction "3_3") (pintype "passive"))
      (node (ref "U1") (pin "4") (pinfunction "SENSE1_4") (pintype "input"))
    )
    (net (code "26") (name "Net-(U1-SENSE2)") (class "Default")
      (node (ref "R5") (pin "3") (pinfunction "3_3") (pintype "passive"))
      (node (ref "U1") (pin "33") (pinfunction "SENSE2_33") (pintype "input"))
    )
    (net (code "27") (name "Net-(U1-TMR1)") (class "Default")
      (node (ref "C13") (pin "1") (pinfunction "1_1") (pintype "passive"))
      (node (ref "U1") (pin "11") (pinfunction "TMR1_11") (pintype "bidirectional"))
    )
    (net (code "28") (name "Net-(U1-TMR2)") (class "Default")
      (node (ref "C8") (pin "1") (pinfunction "1_1") (pintype "passive"))
      (node (ref "U1") (pin "26") (pinfunction "TMR2_26") (pintype "bidirectional"))
    )
    (net (code "29") (name "Net-(U1-UVF1)") (class "Default")
      (node (ref "R14") (pin "2") (pinfunction "2_2") (pintype "passive"))
      (node (ref "R9") (pin "1") (pinfunction "1_1") (pintype "passive"))
      (node (ref "U1") (pin "8") (pinfunction "UVF1_8") (pintype "input"))
    )
    (net (code "30") (name "Net-(U1-UVF2)") (class "Default")
      (node (ref "R15") (pin "1") (pinfunction "1_1") (pintype "passive"))
      (node (ref "R7") (pin "2") (pinfunction "2_2") (pintype "passive"))
      (node (ref "U1") (pin "29") (pinfunction "UVF2_29") (pintype "input"))
    )
    (net (code "31") (name "Net-(U1-UVR1)") (class "Default")
      (node (ref "R10") (pin "2") (pinfunction "2_2") (pintype "passive"))
      (node (ref "R14") (pin "1") (pinfunction "1_1") (pintype "passive"))
      (node (ref "U1") (pin "9") (pinfunction "UVR1_9") (pintype "input"))
    )
    (net (code "32") (name "Net-(U1-UVR2)") (class "Default")
      (node (ref "R16") (pin "2") (pinfunction "2_2") (pintype "passive"))
      (node (ref "R7") (pin "1") (pinfunction "1_1") (pintype "passive"))
      (node (ref "U1") (pin "28") (pinfunction "UVR2_28") (pintype "input"))
    )
    (net (code "33") (name "OUT") (class "Default")
      (node (ref "J1") (pin "3") (pinfunction "3_3") (pintype "passive"))
      (node (ref "J1") (pin "4") (pinfunction "4_4") (pintype "passive"))
      (node (ref "TP7") (pin "1") (pinfunction "1_1") (pintype "passive"))
      (node (ref "XF2") (pin "3") (pinfunction "2_3") (pintype "passive"))
      (node (ref "XF2") (pin "4") (pinfunction "2_4") (pintype "passive"))
      (node (ref "XF3") (pin "3") (pinfunction "2_3") (pintype "passive"))
      (node (ref "XF3") (pin "4") (pinfunction "2_4") (pintype "passive"))
    )
    (net (code "34") (name "SOURCE1") (class "Default")
      (node (ref "C6") (pin "1") (pinfunction "1_1") (pintype "passive"))
      (node (ref "Q1") (pin "3") (pinfunction "S_3") (pintype "passive"))
      (node (ref "Q4") (pin "3") (pinfunction "S_3") (pintype "passive"))
      (node (ref "TP10") (pin "1") (pinfunction "1_1") (pintype "passive"))
      (node (ref "U1") (pin "5") (pinfunction "SOURCE1_5") (pintype "input"))
    )
    (net (code "35") (name "SOURCE2") (class "Default")
      (node (ref "C5") (pin "1") (pinfunction "1_1") (pintype "passive"))
      (node (ref "Q2") (pin "3") (pinfunction "S_3") (pintype "passive"))
      (node (ref "Q3") (pin "3") (pinfunction "S_3") (pintype "passive"))
      (node (ref "TP5") (pin "1") (pinfunction "1_1") (pintype "passive"))
      (node (ref "U1") (pin "32") (pinfunction "SOURCE2_32") (pintype "input"))
    )
    (net (code "36") (name "START") (class "Default")
      (node (ref "D3") (pin "A") (pinfunction "A_A") (pintype "passive"))
      (node (ref "J2") (pin "C") (pinfunction "3_C") (pintype "passive"))
      (node (ref "R1") (pin "2") (pinfunction "2_2") (pintype "passive"))
    )
    (net (code "37") (name "unconnected-(J3-Pad3)") (class "Default")
      (node (ref "J3") (pin "3") (pinfunction "3_3") (pintype "passive"))
    )
    (net (code "38") (name "unconnected-(J3-Pad4)") (class "Default")
      (node (ref "J3") (pin "4") (pinfunction "4_4") (pintype "passive"))
    )
    (net (code "39") (name "unconnected-(U1-CASOUT-Pad18)") (class "Default")
      (node (ref "U1") (pin "18") (pinfunction "CASOUT_18") (pintype "output"))
    )
    (net (code "40") (name "~{SHDN}") (class "Default")
      (node (ref "D2") (pin "C") (pinfunction "C_C") (pintype "passive"))
      (node (ref "D3") (pin "C") (pinfunction "C_C") (pintype "passive"))
      (node (ref "K1") (pin "3") (pinfunction "CONTROL+_3") (pintype "passive"))
      (node (ref "R3") (pin "2") (pinfunction "2_2") (pintype "passive"))
      (node (ref "TP11") (pin "1") (pinfunction "1_1") (pintype "passive"))
      (node (ref "U1") (pin "12") (pinfunction "~{DISABLE1}_12") (pintype "input"))
      (node (ref "U1") (pin "21") (pinfunction "~{SHDN}_21") (pintype "input"))
      (node (ref "U1") (pin "25") (pinfunction "~{DISABLE2}_25") (pintype "input"))
    )
  )
)
